# EMMC_NAND_FLASH.net
KiCad netlist of a schematic drawn in Altium Designer
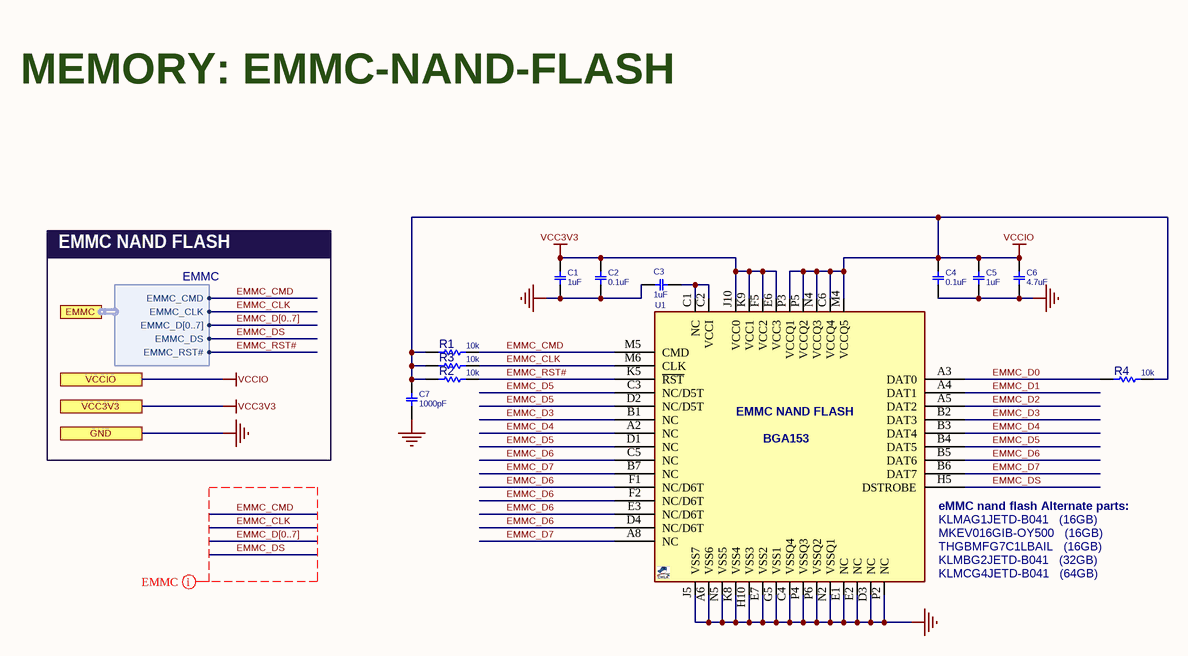
[diagram p0: EMMC_NAND_FLASH.SchDoc]

(export (version "E")
  (design (tool "Eeschema 10.0.6"))
  (components
    (comp (ref "C1")
      (value "1uF")
      (footprint "C0402")
      (description "CAP, MLCC")
      (fields (field (name "MANF_P#") "GMK105ABJ105KV-F") (field (name "MANF") "Taiyo Yuden"))
      (libsource (lib "passive_smd") (part "CAP_SMD_MLCC"))
    )
    (comp (ref "C2")
      (value "0.1uF")
      (footprint "C0402")
      (description "CAP, MLCC")
      (fields (field (name "MANF_P#") "GRM155R61E104") (field (name "MANF") "Murata"))
      (libsource (lib "passive_smd") (part "CAP_SMD_MLCC"))
    )
    (comp (ref "C3")
      (value "1uF")
      (footprint "C0402")
      (description "CAP, MLCC")
      (fields (field (name "MANF_P#") "GMK105ABJ105KV-F") (field (name "MANF") "Taiyo Yuden"))
      (libsource (lib "passive_smd") (part "CAP_SMD_MLCC"))
    )
    (comp (ref "C4")
      (value "0.1uF")
      (footprint "C0402")
      (description "CAP, MLCC")
      (fields (field (name "MANF_P#") "GRM155R61E104") (field (name "MANF") "Murata"))
      (libsource (lib "passive_smd") (part "CAP_SMD_MLCC"))
    )
    (comp (ref "C5")
      (value "1uF")
      (footprint "C0402")
      (description "CAP, MLCC")
      (fields (field (name "MANF_P#") "GMK105ABJ105KV-F") (field (name "MANF") "Taiyo Yuden"))
      (libsource (lib "passive_smd") (part "CAP_SMD_MLCC"))
    )
    (comp (ref "C6")
      (value "4.7uF")
      (footprint "C0402")
      (description "CAP, MLCC")
      (fields (field (name "MANF_P#") "CL05A475MP5NRNC") (field (name "MANF") "Samsung"))
      (libsource (lib "passive_smd") (part "CAP_SMD_MLCC"))
    )
    (comp (ref "C7")
      (value "1000pF")
      (footprint "C0402")
      (description "CAP, MLCC")
      (fields (field (name "MANF_P#") "CC0402JRNPO9BN102") (field (name "MANF") "Yageo"))
      (libsource (lib "mlcc_smd_passive") (part "CAP_SMD_MLCC"))
    )
    (comp (ref "R1")
      (value "10k")
      (footprint "R0402")
      (description "RESISTOR, SMD")
      (libsource (lib "passive_res_smd") (part "RES_SMD"))
    )
    (comp (ref "R2")
      (value "10k")
      (footprint "R0402")
      (description "RESISTOR, SMD")
      (libsource (lib "passive_res_smd") (part "RES_SMD"))
    )
    (comp (ref "R3")
      (value "10k")
      (footprint "R0402")
      (description "RESISTOR, SMD")
      (libsource (lib "passive_res_smd") (part "RES_SMD"))
    )
    (comp (ref "R4")
      (value "10k")
      (footprint "R0402")
      (description "RESISTOR, SMD")
      (libsource (lib "passive_res_smd") (part "RES_SMD"))
    )
    (comp (ref "U1")
      (value "eMMC_16GB")
      (footprint "BGA50_153_EMMC")
      (description "eMMC NAND FLASH, 16GB, 128Gb (16G x 8), 153-VFBGA")
      (fields (field (name "MANF_P#") "KLMAG2GEAC-B031") (field (name "MANF") "Samsung"))
      (libsource (lib "H6") (part "KLMAG2GEAC_16GB_BGA153"))
    )
  )
  (nets
    (net (code "2") (name "/EMMC_CLK") (class "Default")
      (node (ref "R3") (pin "1") (pinfunction "1_1") (pintype "passive"))
      (node (ref "U1") (pin "M6") (pinfunction "CLK_M6") (pintype "passive"))
    )
    (net (code "3") (name "/EMMC_CMD") (class "Default")
      (node (ref "R1") (pin "1") (pinfunction "1_1") (pintype "passive"))
      (node (ref "U1") (pin "M5") (pinfunction "CMD_M5") (pintype "passive"))
    )
    (net (code "4") (name "/EMMC_D0") (class "Default")
      (node (ref "R4") (pin "2") (pinfunction "2_2") (pintype "passive"))
      (node (ref "U1") (pin "A3") (pinfunction "DAT0_A3") (pintype "passive"))
    )
    (net (code "5") (name "/EMMC_D1") (class "Default")
      (node (ref "U1") (pin "A4") (pinfunction "DAT1_A4") (pintype "passive"))
    )
    (net (code "6") (name "/EMMC_D2") (class "Default")
      (node (ref "U1") (pin "A5") (pinfunction "DAT2_A5") (pintype "passive"))
    )
    (net (code "7") (name "/EMMC_D3") (class "Default")
      (node (ref "U1") (pin "B1") (pinfunction "NC_B1") (pintype "passive"))
      (node (ref "U1") (pin "B2") (pinfunction "DAT3_B2") (pintype "passive"))
    )
    (net (code "8") (name "/EMMC_D4") (class "Default")
      (node (ref "U1") (pin "A2") (pinfunction "NC_A2") (pintype "passive"))
      (node (ref "U1") (pin "B3") (pinfunction "DAT4_B3") (pintype "passive"))
    )
    (net (code "9") (name "/EMMC_D5") (class "Default")
      (node (ref "U1") (pin "B4") (pinfunction "DAT5_B4") (pintype "passive"))
      (node (ref "U1") (pin "C3") (pinfunction "NC/D5T_C3") (pintype "passive"))
      (node (ref "U1") (pin "D1") (pinfunction "NC_D1") (pintype "passive"))
      (node (ref "U1") (pin "D2") (pinfunction "NC/D5T_D2") (pintype "passive"))
    )
    (net (code "10") (name "/EMMC_D6") (class "Default")
      (node (ref "U1") (pin "B5") (pinfunction "DAT6_B5") (pintype "passive"))
      (node (ref "U1") (pin "C5") (pinfunction "NC_C5") (pintype "power_in"))
      (node (ref "U1") (pin "D4") (pinfunction "NC/D6T_D4") (pintype "power_in"))
      (node (ref "U1") (pin "E3") (pinfunction "NC/D6T_E3") (pintype "power_in"))
      (node (ref "U1") (pin "F1") (pinfunction "NC/D6T_F1") (pintype "power_in"))
      (node (ref "U1") (pin "F2") (pinfunction "NC/D6T_F2") (pintype "power_in"))
    )
    (net (code "11") (name "/EMMC_D7") (class "Default")
      (node (ref "U1") (pin "A8") (pinfunction "NC_A8") (pintype "passive"))
      (node (ref "U1") (pin "B6") (pinfunction "DAT7_B6") (pintype "passive"))
      (node (ref "U1") (pin "B7") (pinfunction "NC_B7") (pintype "passive"))
    )
    (net (code "12") (name "/EMMC_DS") (class "Default")
      (node (ref "U1") (pin "H5") (pinfunction "DSTROBE_H5") (pintype "passive"))
    )
    (net (code "14") (name "/EMMC_RST#") (class "Default")
      (node (ref "R2") (pin "1") (pinfunction "1_1") (pintype "passive"))
      (node (ref "U1") (pin "K5") (pinfunction "~{RST}_K5") (pintype "passive"))
    )
    (net (code "16") (name "GND") (class "Default")
      (node (ref "C1") (pin "1") (pinfunction "1_1") (pintype "passive"))
      (node (ref "C2") (pin "1") (pinfunction "1_1") (pintype "passive"))
      (node (ref "C3") (pin "1") (pinfunction "1_1") (pintype "passive"))
      (node (ref "C4") (pin "1") (pinfunction "1_1") (pintype "passive"))
      (node (ref "C5") (pin "1") (pinfunction "1_1") (pintype "passive"))
      (node (ref "C6") (pin "1") (pinfunction "1_1") (pintype "passive"))
      (node (ref "C7") (pin "1") (pinfunction "1_1") (pintype "passive"))
      (node (ref "U1") (pin "A6") (pinfunction "VSS6_A6") (pintype "power_in"))
      (node (ref "U1") (pin "C4") (pinfunction "VSSQ4_C4") (pintype "passive"))
      (node (ref "U1") (pin "D3") (pinfunction "NC_D3") (pintype "power_in"))
      (node (ref "U1") (pin "E1") (pinfunction "NC_E1") (pintype "power_in"))
      (node (ref "U1") (pin "E2") (pinfunction "NC_E2") (pintype "power_in"))
      (node (ref "U1") (pin "E7") (pinfunction "VSS2_E7") (pintype "power_in"))
      (node (ref "U1") (pin "G5") (pinfunction "VSS1_G5") (pintype "power_in"))
      (node (ref "U1") (pin "H10") (pinfunction "VSS3_H10") (pintype "power_in"))
      (node (ref "U1") (pin "J5") (pinfunction "VSS7_J5") (pintype "power_in"))
      (node (ref "U1") (pin "K8") (pinfunction "VSS4_K8") (pintype "power_in"))
      (node (ref "U1") (pin "N2") (pinfunction "VSSQ1_N2") (pintype "power_in"))
      (node (ref "U1") (pin "N5") (pinfunction "VSS5_N5") (pintype "power_in"))
      (node (ref "U1") (pin "P2") (pinfunction "NC_P2") (pintype "power_in"))
      (node (ref "U1") (pin "P4") (pinfunction "VSSQ3_P4") (pintype "power_in"))
      (node (ref "U1") (pin "P6") (pinfunction "VSSQ2_P6") (pintype "power_in"))
    )
    (net (code "17") (name "Net-(U1-VCCI)") (class "Default")
      (node (ref "C3") (pin "2") (pinfunction "2_2") (pintype "passive"))
      (node (ref "U1") (pin "C1") (pinfunction "NC_C1") (pintype "power_in"))
      (node (ref "U1") (pin "C2") (pinfunction "VCCI_C2") (pintype "power_in"))
    )
    (net (code "18") (name "VCC3V3") (class "Default")
      (node (ref "C1") (pin "2") (pinfunction "2_2") (pintype "passive"))
      (node (ref "C2") (pin "2") (pinfunction "2_2") (pintype "passive"))
      (node (ref "U1") (pin "E6") (pinfunction "VCC3_E6") (pintype "power_in"))
      (node (ref "U1") (pin "F5") (pinfunction "VCC2_F5") (pintype "power_in"))
      (node (ref "U1") (pin "J10") (pinfunction "VCC0_J10") (pintype "passive"))
      (node (ref "U1") (pin "K9") (pinfunction "VCC1_K9") (pintype "power_in"))
    )
    (net (code "19") (name "VCCIO") (class "Default")
      (node (ref "C4") (pin "2") (pinfunction "2_2") (pintype "passive"))
      (node (ref "C5") (pin "2") (pinfunction "2_2") (pintype "passive"))
      (node (ref "C6") (pin "2") (pinfunction "2_2") (pintype "passive"))
      (node (ref "C7") (pin "2") (pinfunction "2_2") (pintype "passive"))
      (node (ref "R1") (pin "2") (pinfunction "2_2") (pintype "passive"))
      (node (ref "R2") (pin "2") (pinfunction "2_2") (pintype "passive"))
      (node (ref "R3") (pin "2") (pinfunction "2_2") (pintype "passive"))
      (node (ref "R4") (pin "1") (pinfunction "1_1") (pintype "passive"))
      (node (ref "U1") (pin "C6") (pinfunction "VCCQ4_C6") (pintype "passive"))
      (node (ref "U1") (pin "M4") (pinfunction "VCCQ5_M4") (pintype "power_in"))
      (node (ref "U1") (pin "N4") (pinfunction "VCCQ3_N4") (pintype "power_in"))
      (node (ref "U1") (pin "P3") (pinfunction "VCCQ1_P3") (pintype "power_in"))
      (node (ref "U1") (pin "P5") (pinfunction "VCCQ2_P5") (pintype "power_in"))
    )
  )
)
